# Modular.net
KiCad netlist of a schematic drawn in Altium Designer
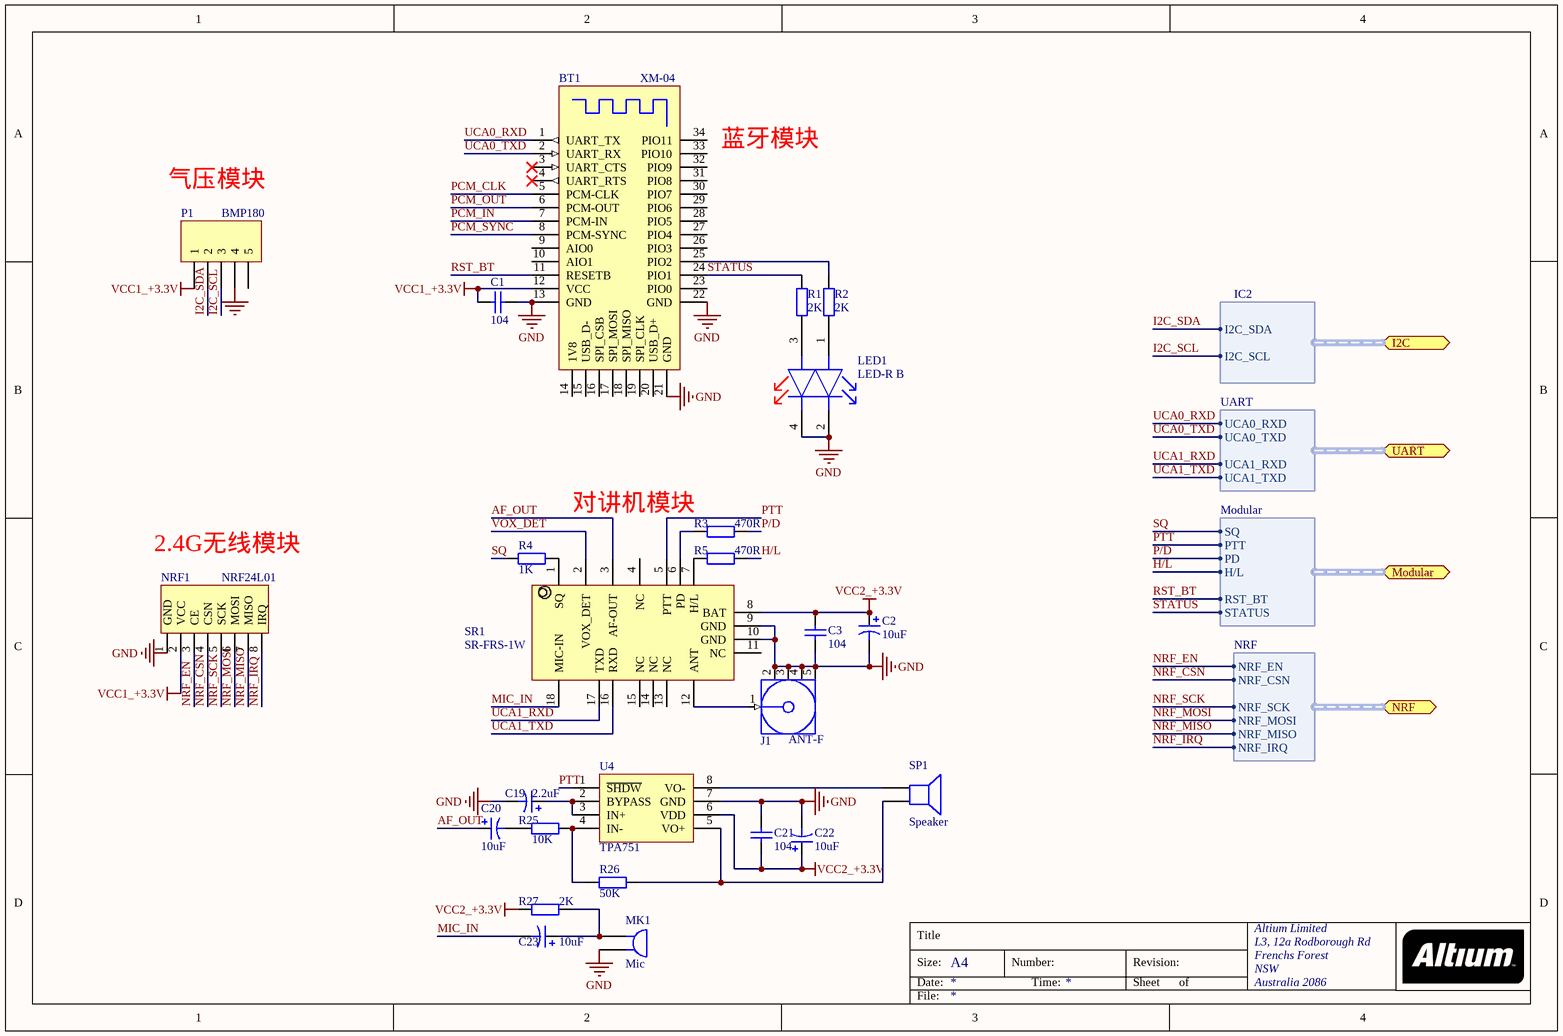
[diagram p0: Modular.SchDoc]

(export (version "E")
  (design (tool "Eeschema 10.0.6"))
  (components
    (comp (ref "BT1") (value "XM-04") (footprint "XM-04") (libsource (lib "BT1-SCH") (part "XM-04")))
    (comp (ref "C1")
      (value "104")
      (footprint "C0805")
      (description "Capacitor")
      (fields (field (name "Comment") "Cap") (field (name "PUBLISHER") "Altium Limited"))
      (libsource (lib "Miscellaneous Devices") (part "Cap"))
    )
    (comp (ref "C2")
      (value "10uF")
      (footprint "SMA-C")
      (description "Polarized Capacitor (Radial)")
      (fields (field (name "Comment") "Cap Pol1") (field (name "PUBLISHER") "Altium Limited"))
      (libsource (lib "xxxlzjxxx Devices") (part "Cap Pol1"))
    )
    (comp (ref "C3")
      (value "104")
      (footprint "C0805")
      (description "Capacitor")
      (fields (field (name "Comment") "Cap") (field (name "PUBLISHER") "Altium Limited"))
      (libsource (lib "Miscellaneous Devices") (part "Cap"))
    )
    (comp (ref "C19")
      (value "2.2uF")
      (footprint "C3216A")
      (description "Polarized Capacitor (Radial)")
      (fields (field (name "Comment") "Cap Pol1") (field (name "PUBLISHER") "Altium Limited"))
      (libsource (lib "xxxlzjxxx Devices") (part "Cap Pol1"))
    )
    (comp (ref "C20")
      (value "10uF")
      (footprint "SMA-C")
      (description "Polarized Capacitor (Radial)")
      (fields (field (name "Comment") "Cap Pol1") (field (name "PUBLISHER") "Altium Limited"))
      (libsource (lib "xxxlzjxxx Devices") (part "Cap Pol1"))
    )
    (comp (ref "C21")
      (value "104")
      (footprint "C0805")
      (description "Capacitor")
      (fields (field (name "Comment") "Cap") (field (name "PUBLISHER") "Altium Limited"))
      (libsource (lib "Miscellaneous Devices") (part "Cap"))
    )
    (comp (ref "C22")
      (value "10uF")
      (footprint "SMA-C")
      (description "Polarized Capacitor (Radial)")
      (fields (field (name "Comment") "Cap Pol1") (field (name "PUBLISHER") "Altium Limited"))
      (libsource (lib "xxxlzjxxx Devices") (part "Cap Pol1"))
    )
    (comp (ref "C23")
      (value "10uF")
      (footprint "SMA-C")
      (description "Polarized Capacitor (Radial)")
      (fields (field (name "Comment") "Cap Pol1") (field (name "PUBLISHER") "Altium Limited"))
      (libsource (lib "xxxlzjxxx Devices") (part "Cap Pol1"))
    )
    (comp (ref "J1")
      (value "ANT-F")
      (footprint "MCX5.08-H5")
      (fields (field (name "PUBLISHER") "Altium Limited"))
      (libsource (lib "Miscellaneous Connectors") (part "COAX-F"))
    )
    (comp (ref "LED1")
      (value "LED-R B")
      (footprint "0805LED - r b")
      (libsource (lib "FR5969v1.0") (part "LED-R B"))
    )
    (comp (ref "MK1")
      (value "Mic")
      (footprint "PIN2")
      (description "Microphone")
      (fields (field (name "PUBLISHER") "Altium Limited"))
      (libsource (lib "xxxlzjxxx Devices") (part "Mic1"))
    )
    (comp (ref "NRF1")
      (value "NRF24L01")
      (footprint "NRF24L01")
      (libsource (lib "xxxlzjxxx Devices") (part "NRF24L01"))
    )
    (comp (ref "P1")
      (value "BMP180")
      (footprint "BMP-180")
      (description "Header, 5-Pin")
      (fields (field (name "PUBLISHER") "Altium Limited"))
      (libsource (lib "Miscellaneous Connectors") (part "Header 5"))
    )
    (comp (ref "R1")
      (value "2K")
      (footprint "R0805")
      (description "Resistor")
      (fields (field (name "Comment") "Res2") (field (name "PUBLISHER") "Altium Limited"))
      (libsource (lib "Miscellaneous Devices") (part "Res2"))
    )
    (comp (ref "R2")
      (value "2K")
      (footprint "R0805")
      (description "Resistor")
      (fields (field (name "Comment") "Res2") (field (name "PUBLISHER") "Altium Limited"))
      (libsource (lib "Miscellaneous Devices") (part "Res2"))
    )
    (comp (ref "R3")
      (value "470R")
      (footprint "R0805")
      (description "Resistor")
      (fields (field (name "Comment") "Res2") (field (name "PUBLISHER") "Altium Limited"))
      (libsource (lib "") (part "Res2_1"))
    )
    (comp (ref "R4")
      (value "1K")
      (footprint "R0805")
      (description "Resistor")
      (fields (field (name "Comment") "Res2") (field (name "PUBLISHER") "Altium Limited"))
      (libsource (lib "") (part "Res2_1"))
    )
    (comp (ref "R5")
      (value "470R")
      (footprint "R0805")
      (description "Resistor")
      (fields (field (name "Comment") "Res2") (field (name "PUBLISHER") "Altium Limited"))
      (libsource (lib "") (part "Res2_2"))
    )
    (comp (ref "R25")
      (value "10K")
      (footprint "R0805")
      (description "Resistor")
      (fields (field (name "Comment") "Res2") (field (name "PUBLISHER") "Altium Limited"))
      (libsource (lib "") (part "Res2_1"))
    )
    (comp (ref "R26")
      (value "50K")
      (footprint "R0805")
      (description "Resistor")
      (fields (field (name "Comment") "Res2") (field (name "PUBLISHER") "Altium Limited"))
      (libsource (lib "") (part "Res2_1"))
    )
    (comp (ref "R27")
      (value "2K")
      (footprint "R0805")
      (description "Resistor")
      (fields (field (name "Comment") "Res2") (field (name "PUBLISHER") "Altium Limited"))
      (libsource (lib "") (part "Res2_1"))
    )
    (comp (ref "SP1")
      (value "Speaker")
      (footprint "PIN2")
      (description "Loudspeaker")
      (fields (field (name "PUBLISHER") "Altium Limited"))
      (libsource (lib "xxxlzjxxx Devices") (part "Speaker"))
    )
    (comp (ref "SR1")
      (value "SR-FRS-1W")
      (footprint "SR-FRS-1W")
      (libsource (lib "BTRF_betaV1.0") (part "SR-FRS-1W"))
    )
    (comp (ref "U4")
      (value "TPA751")
      (footprint "SO-8")
      (description "700mW AB类OP")
      (libsource (lib "FR5969v1.0") (part "TPA751"))
    )
  )
  (nets
    (net (code "5") (name "/AF_OUT") (class "Default")
      (node (ref "C20") (pin "1") (pinfunction "1_1") (pintype "passive"))
      (node (ref "SR1") (pin "3") (pinfunction "AF-OUT_3") (pintype "passive"))
    )
    (net (code "6") (name "/H{slash}L") (class "Default")
      (node (ref "R5") (pin "2") (pinfunction "2_2") (pintype "passive"))
    )
    (net (code "7") (name "/I2C_SCL") (class "Default")
      (node (ref "P1") (pin "3") (pinfunction "3_3") (pintype "passive"))
    )
    (net (code "8") (name "/I2C_SDA") (class "Default")
      (node (ref "P1") (pin "2") (pinfunction "2_2") (pintype "passive"))
    )
    (net (code "9") (name "/MIC_IN") (class "Default")
      (node (ref "C23") (pin "2") (pinfunction "2_2") (pintype "passive"))
      (node (ref "SR1") (pin "18") (pinfunction "MIC-IN_18") (pintype "passive"))
    )
    (net (code "10") (name "/NRF_CSN") (class "Default")
      (node (ref "NRF1") (pin "4") (pinfunction "CSN_4") (pintype "passive"))
    )
    (net (code "11") (name "/NRF_EN") (class "Default")
      (node (ref "NRF1") (pin "3") (pinfunction "CE_3") (pintype "passive"))
    )
    (net (code "12") (name "/NRF_IRQ") (class "Default")
      (node (ref "NRF1") (pin "8") (pinfunction "IRQ_8") (pintype "passive"))
    )
    (net (code "13") (name "/NRF_MISO") (class "Default")
      (node (ref "NRF1") (pin "7") (pinfunction "MISO_7") (pintype "passive"))
    )
    (net (code "14") (name "/NRF_MOSI") (class "Default")
      (node (ref "NRF1") (pin "6") (pinfunction "MOSI_6") (pintype "passive"))
    )
    (net (code "15") (name "/NRF_SCK") (class "Default")
      (node (ref "NRF1") (pin "5") (pinfunction "SCK_5") (pintype "passive"))
    )
    (net (code "16") (name "/PCM_CLK") (class "Default")
      (node (ref "BT1") (pin "5") (pinfunction "PCM-CLK_5") (pintype "passive"))
    )
    (net (code "17") (name "/PCM_IN") (class "Default")
      (node (ref "BT1") (pin "7") (pinfunction "PCM-IN_7") (pintype "passive"))
    )
    (net (code "18") (name "/PCM_OUT") (class "Default")
      (node (ref "BT1") (pin "6") (pinfunction "PCM-OUT_6") (pintype "passive"))
    )
    (net (code "19") (name "/PCM_SYNC") (class "Default")
      (node (ref "BT1") (pin "8") (pinfunction "PCM-SYNC_8") (pintype "passive"))
    )
    (net (code "20") (name "/PTT") (class "Default")
      (node (ref "SR1") (pin "5") (pinfunction "PTT_5") (pintype "passive"))
      (node (ref "U4") (pin "1") (pinfunction "~{SHDW}_1") (pintype "passive"))
    )
    (net (code "21") (name "/P{slash}D") (class "Default")
      (node (ref "R3") (pin "1") (pinfunction "1_1") (pintype "passive"))
    )
    (net (code "22") (name "/RST_BT") (class "Default")
      (node (ref "BT1") (pin "11") (pinfunction "RESETB_11") (pintype "passive"))
    )
    (net (code "23") (name "/SQ") (class "Default")
      (node (ref "R4") (pin "2") (pinfunction "2_2") (pintype "passive"))
    )
    (net (code "24") (name "/STATUS") (class "Default")
      (node (ref "BT1") (pin "24") (pinfunction "PIO1_24") (pintype "passive"))
      (node (ref "R1") (pin "1") (pinfunction "1_1") (pintype "passive"))
    )
    (net (code "25") (name "/UCA0_RXD") (class "Default")
      (node (ref "BT1") (pin "1") (pinfunction "UART_TX_1") (pintype "output"))
    )
    (net (code "26") (name "/UCA0_TXD") (class "Default")
      (node (ref "BT1") (pin "2") (pinfunction "UART_RX_2") (pintype "input"))
    )
    (net (code "27") (name "/UCA1_RXD") (class "Default")
      (node (ref "SR1") (pin "17") (pinfunction "TXD_17") (pintype "passive"))
    )
    (net (code "28") (name "/UCA1_TXD") (class "Default")
      (node (ref "SR1") (pin "16") (pinfunction "RXD_16") (pintype "passive"))
    )
    (net (code "29") (name "/VOX_DET") (class "Default")
      (node (ref "SR1") (pin "2") (pinfunction "VOX_DET_2") (pintype "passive"))
    )
    (net (code "34") (name "GND") (class "Default")
      (node (ref "BT1") (pin "13") (pinfunction "GND_13") (pintype "passive"))
      (node (ref "BT1") (pin "21") (pinfunction "GND_21") (pintype "passive"))
      (node (ref "BT1") (pin "22") (pinfunction "GND_22") (pintype "passive"))
      (node (ref "C1") (pin "1") (pinfunction "1_1") (pintype "passive"))
      (node (ref "C19") (pin "2") (pinfunction "2_2") (pintype "passive"))
      (node (ref "C2") (pin "2") (pinfunction "2_2") (pintype "passive"))
      (node (ref "C21") (pin "2") (pinfunction "2_2") (pintype "passive"))
      (node (ref "C22") (pin "2") (pinfunction "2_2") (pintype "passive"))
      (node (ref "C3") (pin "2") (pinfunction "2_2") (pintype "passive"))
      (node (ref "J1") (pin "2") (pinfunction "GND_2") (pintype "power_in"))
      (node (ref "J1") (pin "3") (pinfunction "GND_3") (pintype "power_in"))
      (node (ref "J1") (pin "4") (pinfunction "GND_4") (pintype "power_in"))
      (node (ref "J1") (pin "5") (pinfunction "GND_5") (pintype "power_in"))
      (node (ref "LED1") (pin "2") (pinfunction "2_2") (pintype "passive"))
      (node (ref "LED1") (pin "4") (pinfunction "4_4") (pintype "passive"))
      (node (ref "MK1") (pin "2") (pinfunction "2_2") (pintype "passive"))
      (node (ref "NRF1") (pin "1") (pinfunction "GND_1") (pintype "passive"))
      (node (ref "P1") (pin "4") (pinfunction "4_4") (pintype "passive"))
      (node (ref "SR1") (pin "10") (pinfunction "GND_10") (pintype "passive"))
      (node (ref "SR1") (pin "9") (pinfunction "GND_9") (pintype "passive"))
      (node (ref "U4") (pin "7") (pinfunction "GND_7") (pintype "passive"))
    )
    (net (code "35") (name "Net-(BT1-PIO2)") (class "Default")
      (node (ref "BT1") (pin "25") (pinfunction "PIO2_25") (pintype "passive"))
      (node (ref "R2") (pin "1") (pinfunction "1_1") (pintype "passive"))
    )
    (net (code "36") (name "Net-(C20-Pad2)") (class "Default")
      (node (ref "C20") (pin "2") (pinfunction "2_2") (pintype "passive"))
      (node (ref "R25") (pin "2") (pinfunction "2_2") (pintype "passive"))
    )
    (net (code "37") (name "Net-(C23-Pad1)") (class "Default")
      (node (ref "C23") (pin "1") (pinfunction "1_1") (pintype "passive"))
      (node (ref "MK1") (pin "1") (pinfunction "1_1") (pintype "passive"))
      (node (ref "R27") (pin "1") (pinfunction "1_1") (pintype "passive"))
    )
    (net (code "38") (name "Net-(J1-Signal)") (class "Default")
      (node (ref "J1") (pin "1") (pinfunction "Signal_1") (pintype "input"))
      (node (ref "SR1") (pin "12") (pinfunction "ANT_12") (pintype "passive"))
    )
    (net (code "39") (name "Net-(LED1-Pad1)") (class "Default")
      (node (ref "LED1") (pin "1") (pinfunction "1_1") (pintype "passive"))
      (node (ref "R2") (pin "2") (pinfunction "2_2") (pintype "passive"))
    )
    (net (code "40") (name "Net-(LED1-Pad3)") (class "Default")
      (node (ref "LED1") (pin "3") (pinfunction "3_3") (pintype "passive"))
      (node (ref "R1") (pin "2") (pinfunction "2_2") (pintype "passive"))
    )
    (net (code "41") (name "Net-(SR1-H{slash}L)") (class "Default")
      (node (ref "R5") (pin "1") (pinfunction "1_1") (pintype "passive"))
      (node (ref "SR1") (pin "7") (pinfunction "H/L_7") (pintype "passive"))
    )
    (net (code "42") (name "Net-(SR1-PD)") (class "Default")
      (node (ref "R3") (pin "2") (pinfunction "2_2") (pintype "passive"))
      (node (ref "SR1") (pin "6") (pinfunction "PD_6") (pintype "passive"))
    )
    (net (code "43") (name "Net-(SR1-SQ)") (class "Default")
      (node (ref "R4") (pin "1") (pinfunction "1_1") (pintype "passive"))
      (node (ref "SR1") (pin "1") (pinfunction "SQ_1") (pintype "passive"))
    )
    (net (code "44") (name "Net-(U4-BYPASS)") (class "Default")
      (node (ref "C19") (pin "1") (pinfunction "1_1") (pintype "passive"))
      (node (ref "U4") (pin "2") (pinfunction "BYPASS_2") (pintype "passive"))
      (node (ref "U4") (pin "3") (pinfunction "IN+_3") (pintype "passive"))
    )
    (net (code "45") (name "Net-(U4-IN-)") (class "Default")
      (node (ref "R25") (pin "1") (pinfunction "1_1") (pintype "passive"))
      (node (ref "R26") (pin "2") (pinfunction "2_2") (pintype "passive"))
      (node (ref "U4") (pin "4") (pinfunction "IN-_4") (pintype "passive"))
    )
    (net (code "46") (name "Net-(U4-VO+)") (class "Default")
      (node (ref "R26") (pin "1") (pinfunction "1_1") (pintype "passive"))
      (node (ref "SP1") (pin "2") (pinfunction "2_2") (pintype "passive"))
      (node (ref "U4") (pin "5") (pinfunction "VO+_5") (pintype "passive"))
    )
    (net (code "47") (name "Net-(U4-VO-)") (class "Default")
      (node (ref "SP1") (pin "1") (pinfunction "1_1") (pintype "passive"))
      (node (ref "U4") (pin "8") (pinfunction "VO-_8") (pintype "passive"))
    )
    (net (code "48") (name "VCC1_+3.3V") (class "Default")
      (node (ref "BT1") (pin "12") (pinfunction "VCC_12") (pintype "power_in"))
      (node (ref "C1") (pin "2") (pinfunction "2_2") (pintype "passive"))
      (node (ref "NRF1") (pin "2") (pinfunction "VCC_2") (pintype "passive"))
      (node (ref "P1") (pin "1") (pinfunction "1_1") (pintype "passive"))
    )
    (net (code "49") (name "VCC2_+3.3V") (class "Default")
      (node (ref "C2") (pin "1") (pinfunction "1_1") (pintype "passive"))
      (node (ref "C21") (pin "1") (pinfunction "1_1") (pintype "passive"))
      (node (ref "C22") (pin "1") (pinfunction "1_1") (pintype "passive"))
      (node (ref "C3") (pin "1") (pinfunction "1_1") (pintype "passive"))
      (node (ref "R27") (pin "2") (pinfunction "2_2") (pintype "passive"))
      (node (ref "SR1") (pin "8") (pinfunction "BAT_8") (pintype "passive"))
      (node (ref "U4") (pin "6") (pinfunction "VDD_6") (pintype "passive"))
    )
    (net (code "50") (name "unconnected-(BT1-1V8-Pad14)") (class "Default")
      (node (ref "BT1") (pin "14") (pinfunction "1V8_14") (pintype "passive"))
    )
    (net (code "51") (name "unconnected-(BT1-AIO0-Pad9)") (class "Default")
      (node (ref "BT1") (pin "9") (pinfunction "AIO0_9") (pintype "passive"))
    )
    (net (code "52") (name "unconnected-(BT1-AIO1-Pad10)") (class "Default")
      (node (ref "BT1") (pin "10") (pinfunction "AIO1_10") (pintype "passive"))
    )
    (net (code "53") (name "unconnected-(BT1-PIO0-Pad23)") (class "Default")
      (node (ref "BT1") (pin "23") (pinfunction "PIO0_23") (pintype "passive"))
    )
    (net (code "54") (name "unconnected-(BT1-PIO3-Pad26)") (class "Default")
      (node (ref "BT1") (pin "26") (pinfunction "PIO3_26") (pintype "passive"))
    )
    (net (code "55") (name "unconnected-(BT1-PIO4-Pad27)") (class "Default")
      (node (ref "BT1") (pin "27") (pinfunction "PIO4_27") (pintype "passive"))
    )
    (net (code "56") (name "unconnected-(BT1-PIO5-Pad28)") (class "Default")
      (node (ref "BT1") (pin "28") (pinfunction "PIO5_28") (pintype "passive"))
    )
    (net (code "57") (name "unconnected-(BT1-PIO6-Pad29)") (class "Default")
      (node (ref "BT1") (pin "29") (pinfunction "PIO6_29") (pintype "passive"))
    )
    (net (code "58") (name "unconnected-(BT1-PIO7-Pad30)") (class "Default")
      (node (ref "BT1") (pin "30") (pinfunction "PIO7_30") (pintype "passive"))
    )
    (net (code "59") (name "unconnected-(BT1-PIO8-Pad31)") (class "Default")
      (node (ref "BT1") (pin "31") (pinfunction "PIO8_31") (pintype "passive"))
    )
    (net (code "60") (name "unconnected-(BT1-PIO9-Pad32)") (class "Default")
      (node (ref "BT1") (pin "32") (pinfunction "PIO9_32") (pintype "passive"))
    )
    (net (code "61") (name "unconnected-(BT1-PIO10-Pad33)") (class "Default")
      (node (ref "BT1") (pin "33") (pinfunction "PIO10_33") (pintype "passive"))
    )
    (net (code "62") (name "unconnected-(BT1-PIO11-Pad34)") (class "Default")
      (node (ref "BT1") (pin "34") (pinfunction "PIO11_34") (pintype "passive"))
    )
    (net (code "63") (name "unconnected-(BT1-SPI_CLK-Pad19)") (class "Default")
      (node (ref "BT1") (pin "19") (pinfunction "SPI_CLK_19") (pintype "passive"))
    )
    (net (code "64") (name "unconnected-(BT1-SPI_CSB-Pad16)") (class "Default")
      (node (ref "BT1") (pin "16") (pinfunction "SPI_CSB_16") (pintype "passive"))
    )
    (net (code "65") (name "unconnected-(BT1-SPI_MISO-Pad18)") (class "Default")
      (node (ref "BT1") (pin "18") (pinfunction "SPI_MISO_18") (pintype "passive"))
    )
    (net (code "66") (name "unconnected-(BT1-SPI_MOSI-Pad17)") (class "Default")
      (node (ref "BT1") (pin "17") (pinfunction "SPI_MOSI_17") (pintype "passive"))
    )
    (net (code "67") (name "unconnected-(BT1-UART_CTS-Pad3)") (class "Default")
      (node (ref "BT1") (pin "3") (pinfunction "UART_CTS_3") (pintype "input+no_connect"))
    )
    (net (code "68") (name "unconnected-(BT1-UART_RTS-Pad4)") (class "Default")
      (node (ref "BT1") (pin "4") (pinfunction "UART_RTS_4") (pintype "output+no_connect"))
    )
    (net (code "69") (name "unconnected-(BT1-USB_D+-Pad20)") (class "Default")
      (node (ref "BT1") (pin "20") (pinfunction "USB_D+_20") (pintype "passive"))
    )
    (net (code "70") (name "unconnected-(BT1-USB_D--Pad15)") (class "Default")
      (node (ref "BT1") (pin "15") (pinfunction "USB_D-_15") (pintype "passive"))
    )
    (net (code "71") (name "unconnected-(P1-Pad5)") (class "Default")
      (node (ref "P1") (pin "5") (pinfunction "5_5") (pintype "passive"))
    )
    (net (code "72") (name "unconnected-(SR1-NC-Pad4)") (class "Default")
      (node (ref "SR1") (pin "4") (pinfunction "NC_4") (pintype "passive"))
    )
    (net (code "73") (name "unconnected-(SR1-NC-Pad11)") (class "Default")
      (node (ref "SR1") (pin "11") (pinfunction "NC_11") (pintype "passive"))
    )
    (net (code "74") (name "unconnected-(SR1-NC-Pad13)") (class "Default")
      (node (ref "SR1") (pin "13") (pinfunction "NC_13") (pintype "passive"))
    )
    (net (code "75") (name "unconnected-(SR1-NC-Pad14)") (class "Default")
      (node (ref "SR1") (pin "14") (pinfunction "NC_14") (pintype "passive"))
    )
    (net (code "76") (name "unconnected-(SR1-NC-Pad15)") (class "Default")
      (node (ref "SR1") (pin "15") (pinfunction "NC_15") (pintype "passive"))
    )
  )
)
